# prutokomer.net
KiCad netlist of a schematic drawn in EAGLE
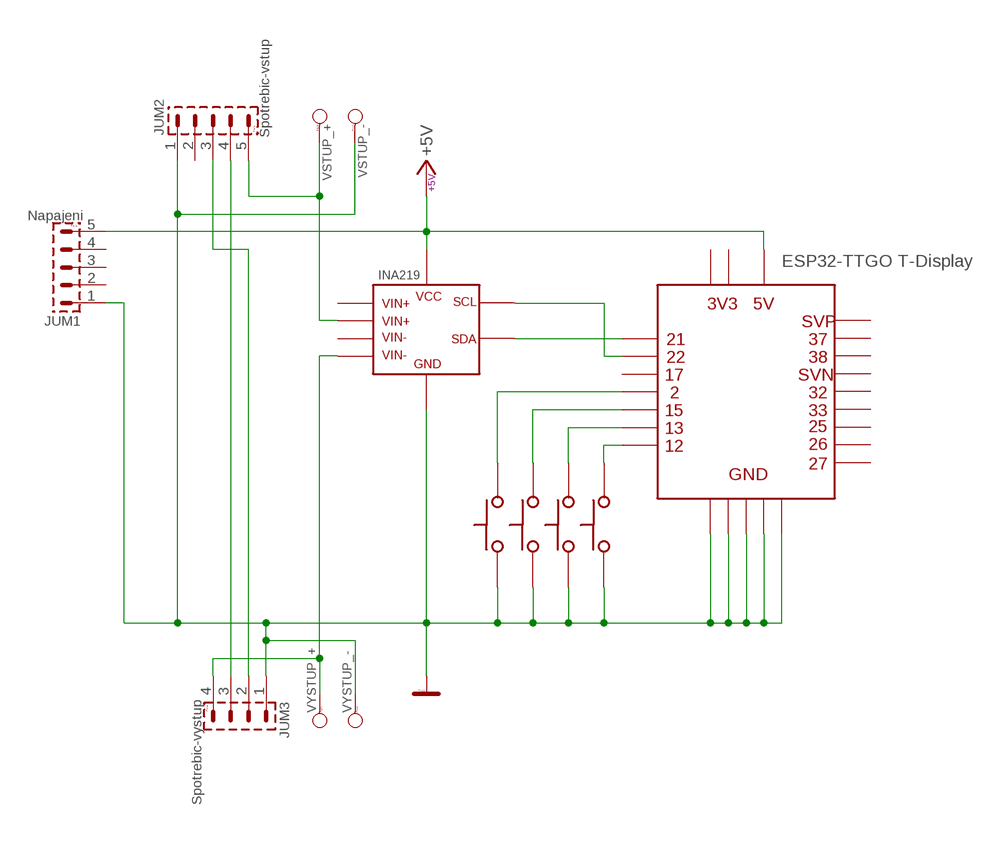
[diagram p0: schematic, sheet 1]

(export (version "E")
  (design (tool "Eeschema 10.0.6"))
  (components
    (comp (ref "JUM1")
      (value "Napajeni")
      (footprint "eagle-import:S1G5_JUM")
      (libsource (lib "eagle-import") (part "S1G5_JUMP"))
    )
    (comp (ref "JUM2")
      (value "Spotrebic-vstup")
      (footprint "eagle-import:S1G5_JUM")
      (libsource (lib "eagle-import") (part "S1G5_JUMP"))
    )
    (comp (ref "JUM3")
      (value "Spotrebic-vystup")
      (footprint "eagle-import:S1G4_JUM")
      (libsource (lib "eagle-import") (part "S1G4_JUMP"))
    )
    (comp (ref "SW1")
      (value "TLACITKO")
      (footprint "eagle-import:TLACITKO")
      (libsource (lib "eagle-import") (part "TLACITKO"))
    )
    (comp (ref "SW2")
      (value "TLACITKO")
      (footprint "eagle-import:TLACITKO")
      (libsource (lib "eagle-import") (part "TLACITKO"))
    )
    (comp (ref "SW3")
      (value "TLACITKO")
      (footprint "eagle-import:TLACITKO")
      (libsource (lib "eagle-import") (part "TLACITKO"))
    )
    (comp (ref "SW4")
      (value "TLACITKO")
      (footprint "eagle-import:TLACITKO")
      (libsource (lib "eagle-import") (part "TLACITKO"))
    )
    (comp (ref "U$1")
      (value "INA219")
      (footprint "eagle-import:INA219")
      (libsource (lib "eagle-import") (part "INA219"))
    )
    (comp (ref "U$2")
      (value "ESP32_TTGOT-DISPLAY")
      (footprint "eagle-import:ESP32-TTGO-TDISPLAY")
      (libsource (lib "eagle-import") (part "ESP32_TTGOT-DISPLAY"))
    )
    (comp (ref "VSTUP_+")
      (value "PAD_1")
      (footprint "eagle-import:PAD_1")
      (libsource (lib "eagle-import") (part "PAD_1"))
    )
    (comp (ref "VSTUP_-")
      (value "PAD_1")
      (footprint "eagle-import:PAD_1")
      (libsource (lib "eagle-import") (part "PAD_1"))
    )
    (comp (ref "VYSTUP_+")
      (value "PAD_1")
      (footprint "eagle-import:PAD_1")
      (libsource (lib "eagle-import") (part "PAD_1"))
    )
    (comp (ref "VYSTUP_-")
      (value "PAD_1")
      (footprint "eagle-import:PAD_1")
      (libsource (lib "eagle-import") (part "PAD_1"))
    )
  )
  (nets
    (net (code "1") (name "+5V") (class "Default")
      (node (ref "JUM1") (pin "5") (pinfunction "5_5") (pintype "passive"))
      (node (ref "U$1") (pin "VCC") (pinfunction "VCC_VCC") (pintype "bidirectional"))
      (node (ref "U$2") (pin "5V") (pinfunction "5V_5V") (pintype "bidirectional"))
    )
    (net (code "2") (name "GND") (class "Default")
      (node (ref "JUM1") (pin "1") (pinfunction "1_1") (pintype "passive"))
      (node (ref "JUM2") (pin "1") (pinfunction "1_1") (pintype "passive"))
      (node (ref "JUM3") (pin "1") (pinfunction "1_1") (pintype "passive"))
      (node (ref "SW1") (pin "1") (pinfunction "1_1") (pintype "bidirectional"))
      (node (ref "SW2") (pin "1") (pinfunction "1_1") (pintype "bidirectional"))
      (node (ref "SW3") (pin "1") (pinfunction "1_1") (pintype "bidirectional"))
      (node (ref "SW4") (pin "1") (pinfunction "1_1") (pintype "bidirectional"))
      (node (ref "U$1") (pin "GND") (pinfunction "GND_GND") (pintype "bidirectional"))
      (node (ref "U$2") (pin "GND1") (pinfunction "GND1_GND1") (pintype "bidirectional"))
      (node (ref "U$2") (pin "GND2") (pinfunction "GND2_GND2") (pintype "bidirectional"))
      (node (ref "U$2") (pin "GND3") (pinfunction "GND3_GND3") (pintype "bidirectional"))
      (node (ref "U$2") (pin "GND4") (pinfunction "GND4_GND4") (pintype "bidirectional"))
      (node (ref "U$2") (pin "GND5") (pinfunction "GND5_GND5") (pintype "bidirectional"))
      (node (ref "VSTUP_-") (pin "1") (pinfunction "1_1") (pintype "passive"))
      (node (ref "VYSTUP_-") (pin "1") (pinfunction "1_1") (pintype "passive"))
    )
    (net (code "3") (name "Net-(JUM2-Pad3)") (class "Default")
      (node (ref "JUM2") (pin "3") (pinfunction "3_3") (pintype "passive"))
      (node (ref "JUM3") (pin "2") (pinfunction "2_2") (pintype "passive"))
    )
    (net (code "4") (name "Net-(JUM2-Pad4)") (class "Default")
      (node (ref "JUM2") (pin "4") (pinfunction "4_4") (pintype "passive"))
      (node (ref "JUM3") (pin "3") (pinfunction "3_3") (pintype "passive"))
    )
    (net (code "5") (name "Net-(SW1-Pad2)") (class "Default")
      (node (ref "SW1") (pin "2") (pinfunction "2_2") (pintype "bidirectional"))
      (node (ref "U$2") (pin "2") (pinfunction "2_2") (pintype "bidirectional"))
    )
    (net (code "6") (name "Net-(SW2-Pad2)") (class "Default")
      (node (ref "SW2") (pin "2") (pinfunction "2_2") (pintype "bidirectional"))
      (node (ref "U$2") (pin "15") (pinfunction "15_15") (pintype "bidirectional"))
    )
    (net (code "7") (name "Net-(SW3-Pad2)") (class "Default")
      (node (ref "SW3") (pin "2") (pinfunction "2_2") (pintype "bidirectional"))
      (node (ref "U$2") (pin "13") (pinfunction "13_13") (pintype "bidirectional"))
    )
    (net (code "8") (name "Net-(SW4-Pad2)") (class "Default")
      (node (ref "SW4") (pin "2") (pinfunction "2_2") (pintype "bidirectional"))
      (node (ref "U$2") (pin "12") (pinfunction "12_12") (pintype "bidirectional"))
    )
    (net (code "9") (name "Net-(U$1-.VIN+)") (class "Default")
      (node (ref "JUM2") (pin "5") (pinfunction "5_5") (pintype "passive"))
      (node (ref "U$1") (pin "..VIN+") (pinfunction ".VIN+_..VIN+") (pintype "bidirectional"))
      (node (ref "VSTUP_+") (pin "1") (pinfunction "1_1") (pintype "passive"))
    )
    (net (code "10") (name "Net-(U$1-.VIN-)") (class "Default")
      (node (ref "JUM3") (pin "4") (pinfunction "4_4") (pintype "passive"))
      (node (ref "U$1") (pin "..VIN-") (pinfunction ".VIN-_..VIN-") (pintype "bidirectional"))
      (node (ref "VYSTUP_+") (pin "1") (pinfunction "1_1") (pintype "passive"))
    )
    (net (code "11") (name "Net-(U$1-PadSCL)") (class "Default")
      (node (ref "U$1") (pin "SCL") (pinfunction "SCL_SCL") (pintype "bidirectional"))
      (node (ref "U$2") (pin "22") (pinfunction "22_22") (pintype "bidirectional"))
    )
    (net (code "12") (name "Net-(U$1-PadSDA)") (class "Default")
      (node (ref "U$1") (pin "SDA") (pinfunction "SDA_SDA") (pintype "bidirectional"))
      (node (ref "U$2") (pin "21") (pinfunction "21_21") (pintype "bidirectional"))
    )
    (net (code "13") (name "unconnected-(JUM1-Pad2)") (class "Default")
      (node (ref "JUM1") (pin "2") (pinfunction "2_2") (pintype "passive"))
    )
    (net (code "14") (name "unconnected-(JUM1-Pad3)") (class "Default")
      (node (ref "JUM1") (pin "3") (pinfunction "3_3") (pintype "passive"))
    )
    (net (code "15") (name "unconnected-(JUM1-Pad4)") (class "Default")
      (node (ref "JUM1") (pin "4") (pinfunction "4_4") (pintype "passive"))
    )
    (net (code "16") (name "unconnected-(JUM2-Pad2)") (class "Default")
      (node (ref "JUM2") (pin "2") (pinfunction "2_2") (pintype "passive"))
    )
    (net (code "17") (name "unconnected-(U$1-PadVIN+)") (class "Default")
      (node (ref "U$1") (pin "VIN+") (pinfunction "VIN+_VIN+") (pintype "bidirectional"))
    )
    (net (code "18") (name "unconnected-(U$1-PadVIN-)") (class "Default")
      (node (ref "U$1") (pin "VIN-") (pinfunction "VIN-_VIN-") (pintype "bidirectional"))
    )
    (net (code "19") (name "unconnected-(U$2-3V3_2-Pad3V3-)") (class "Default")
      (node (ref "U$2") (pin "3V3-") (pinfunction "3V3_2_3V3-") (pintype "bidirectional"))
    )
    (net (code "20") (name "unconnected-(U$2-Pad3V3)") (class "Default")
      (node (ref "U$2") (pin "3V3") (pinfunction "3V3_3V3") (pintype "bidirectional"))
    )
    (net (code "21") (name "unconnected-(U$2-Pad17)") (class "Default")
      (node (ref "U$2") (pin "17") (pinfunction "17_17") (pintype "bidirectional"))
    )
    (net (code "22") (name "unconnected-(U$2-Pad25)") (class "Default")
      (node (ref "U$2") (pin "25") (pinfunction "25_25") (pintype "bidirectional"))
    )
    (net (code "23") (name "unconnected-(U$2-Pad26)") (class "Default")
      (node (ref "U$2") (pin "26") (pinfunction "26_26") (pintype "bidirectional"))
    )
    (net (code "24") (name "unconnected-(U$2-Pad27)") (class "Default")
      (node (ref "U$2") (pin "27") (pinfunction "27_27") (pintype "bidirectional"))
    )
    (net (code "25") (name "unconnected-(U$2-Pad32)") (class "Default")
      (node (ref "U$2") (pin "32") (pinfunction "32_32") (pintype "bidirectional"))
    )
    (net (code "26") (name "unconnected-(U$2-Pad33)") (class "Default")
      (node (ref "U$2") (pin "33") (pinfunction "33_33") (pintype "bidirectional"))
    )
    (net (code "27") (name "unconnected-(U$2-Pad37)") (class "Default")
      (node (ref "U$2") (pin "37") (pinfunction "37_37") (pintype "bidirectional"))
    )
    (net (code "28") (name "unconnected-(U$2-Pad38)") (class "Default")
      (node (ref "U$2") (pin "38") (pinfunction "38_38") (pintype "bidirectional"))
    )
    (net (code "29") (name "unconnected-(U$2-PadSVN)") (class "Default")
      (node (ref "U$2") (pin "SVN") (pinfunction "SVN_SVN") (pintype "bidirectional"))
    )
    (net (code "30") (name "unconnected-(U$2-PadSVP)") (class "Default")
      (node (ref "U$2") (pin "SVP") (pinfunction "SVP_SVP") (pintype "bidirectional"))
    )
  )
)
